# Resistor_Board.net
KiCad netlist of a schematic drawn in EAGLE
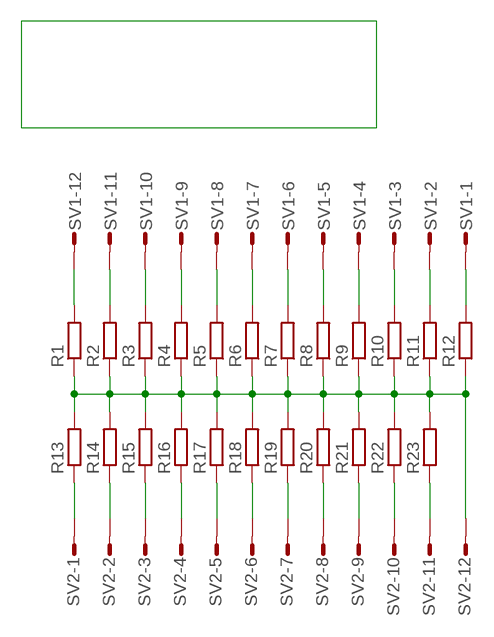
[diagram p0: schematic, sheet 1]

(export (version "E")
  (design (tool "Eeschema 10.0.6"))
  (components
    (comp (ref "R1")
      (value "R-EU_0207/10")
      (footprint "eagle-import:0207_10")
      (libsource (lib "eagle-import") (part "R-EU_0207/10"))
    )
    (comp (ref "R2")
      (value "R-EU_0207/10")
      (footprint "eagle-import:0207_10")
      (libsource (lib "eagle-import") (part "R-EU_0207/10"))
    )
    (comp (ref "R3")
      (value "R-EU_0207/10")
      (footprint "eagle-import:0207_10")
      (libsource (lib "eagle-import") (part "R-EU_0207/10"))
    )
    (comp (ref "R4")
      (value "R-EU_0207/10")
      (footprint "eagle-import:0207_10")
      (libsource (lib "eagle-import") (part "R-EU_0207/10"))
    )
    (comp (ref "R5")
      (value "R-EU_0207/10")
      (footprint "eagle-import:0207_10")
      (libsource (lib "eagle-import") (part "R-EU_0207/10"))
    )
    (comp (ref "R6")
      (value "R-EU_0207/10")
      (footprint "eagle-import:0207_10")
      (libsource (lib "eagle-import") (part "R-EU_0207/10"))
    )
    (comp (ref "R7")
      (value "R-EU_0207/10")
      (footprint "eagle-import:0207_10")
      (libsource (lib "eagle-import") (part "R-EU_0207/10"))
    )
    (comp (ref "R8")
      (value "R-EU_0207/10")
      (footprint "eagle-import:0207_10")
      (libsource (lib "eagle-import") (part "R-EU_0207/10"))
    )
    (comp (ref "R9")
      (value "R-EU_0207/10")
      (footprint "eagle-import:0207_10")
      (libsource (lib "eagle-import") (part "R-EU_0207/10"))
    )
    (comp (ref "R10")
      (value "R-EU_0207/10")
      (footprint "eagle-import:0207_10")
      (libsource (lib "eagle-import") (part "R-EU_0207/10"))
    )
    (comp (ref "R11")
      (value "R-EU_0207/10")
      (footprint "eagle-import:0207_10")
      (libsource (lib "eagle-import") (part "R-EU_0207/10"))
    )
    (comp (ref "R12")
      (value "R-EU_0207/10")
      (footprint "eagle-import:0207_10")
      (libsource (lib "eagle-import") (part "R-EU_0207/10"))
    )
    (comp (ref "R13")
      (value "R-EU_0207/10")
      (footprint "eagle-import:0207_10")
      (libsource (lib "eagle-import") (part "R-EU_0207/10"))
    )
    (comp (ref "R14")
      (value "R-EU_0207/10")
      (footprint "eagle-import:0207_10")
      (libsource (lib "eagle-import") (part "R-EU_0207/10"))
    )
    (comp (ref "R15")
      (value "R-EU_0207/10")
      (footprint "eagle-import:0207_10")
      (libsource (lib "eagle-import") (part "R-EU_0207/10"))
    )
    (comp (ref "R16")
      (value "R-EU_0207/10")
      (footprint "eagle-import:0207_10")
      (libsource (lib "eagle-import") (part "R-EU_0207/10"))
    )
    (comp (ref "R17")
      (value "R-EU_0207/10")
      (footprint "eagle-import:0207_10")
      (libsource (lib "eagle-import") (part "R-EU_0207/10"))
    )
    (comp (ref "R18")
      (value "R-EU_0207/10")
      (footprint "eagle-import:0207_10")
      (libsource (lib "eagle-import") (part "R-EU_0207/10"))
    )
    (comp (ref "R19")
      (value "R-EU_0207/10")
      (footprint "eagle-import:0207_10")
      (libsource (lib "eagle-import") (part "R-EU_0207/10"))
    )
    (comp (ref "R20")
      (value "R-EU_0207/10")
      (footprint "eagle-import:0207_10")
      (libsource (lib "eagle-import") (part "R-EU_0207/10"))
    )
    (comp (ref "R21")
      (value "R-EU_0207/10")
      (footprint "eagle-import:0207_10")
      (libsource (lib "eagle-import") (part "R-EU_0207/10"))
    )
    (comp (ref "R22")
      (value "R-EU_0207/10")
      (footprint "eagle-import:0207_10")
      (libsource (lib "eagle-import") (part "R-EU_0207/10"))
    )
    (comp (ref "R23")
      (value "R-EU_0207/10")
      (footprint "eagle-import:0207_10")
      (libsource (lib "eagle-import") (part "R-EU_0207/10"))
    )
    (comp (ref "SV1")
      (value "S12P")
      (footprint "eagle-import:S12P")
      (libsource (lib "eagle-import") (part "S12P"))
    )
    (comp (ref "SV2")
      (value "S12P")
      (footprint "eagle-import:S12P")
      (libsource (lib "eagle-import") (part "S12P"))
    )
  )
  (nets
    (net (code "1") (name "Net-(SV1A-S)") (class "Default")
      (node (ref "R12") (pin "2") (pinfunction "2_2") (pintype "passive"))
      (node (ref "SV1") (pin "1") (pinfunction "S_1") (pintype "passive"))
    )
    (net (code "2") (name "Net-(SV1B-S)") (class "Default")
      (node (ref "R3") (pin "2") (pinfunction "2_2") (pintype "passive"))
      (node (ref "SV1") (pin "10") (pinfunction "S_10") (pintype "passive"))
    )
    (net (code "3") (name "Net-(SV1C-S)") (class "Default")
      (node (ref "R2") (pin "2") (pinfunction "2_2") (pintype "passive"))
      (node (ref "SV1") (pin "11") (pinfunction "S_11") (pintype "passive"))
    )
    (net (code "4") (name "Net-(SV1D-S)") (class "Default")
      (node (ref "R1") (pin "2") (pinfunction "2_2") (pintype "passive"))
      (node (ref "SV1") (pin "12") (pinfunction "S_12") (pintype "passive"))
    )
    (net (code "5") (name "Net-(SV1E-S)") (class "Default")
      (node (ref "R11") (pin "2") (pinfunction "2_2") (pintype "passive"))
      (node (ref "SV1") (pin "2") (pinfunction "S_2") (pintype "passive"))
    )
    (net (code "6") (name "Net-(SV1F-S)") (class "Default")
      (node (ref "R10") (pin "2") (pinfunction "2_2") (pintype "passive"))
      (node (ref "SV1") (pin "3") (pinfunction "S_3") (pintype "passive"))
    )
    (net (code "7") (name "Net-(SV1G-S)") (class "Default")
      (node (ref "R9") (pin "2") (pinfunction "2_2") (pintype "passive"))
      (node (ref "SV1") (pin "4") (pinfunction "S_4") (pintype "passive"))
    )
    (net (code "8") (name "Net-(SV1H-S)") (class "Default")
      (node (ref "R8") (pin "2") (pinfunction "2_2") (pintype "passive"))
      (node (ref "SV1") (pin "5") (pinfunction "S_5") (pintype "passive"))
    )
    (net (code "9") (name "Net-(SV1I-S)") (class "Default")
      (node (ref "R7") (pin "2") (pinfunction "2_2") (pintype "passive"))
      (node (ref "SV1") (pin "6") (pinfunction "S_6") (pintype "passive"))
    )
    (net (code "10") (name "Net-(SV1J-S)") (class "Default")
      (node (ref "R6") (pin "2") (pinfunction "2_2") (pintype "passive"))
      (node (ref "SV1") (pin "7") (pinfunction "S_7") (pintype "passive"))
    )
    (net (code "11") (name "Net-(SV1K-S)") (class "Default")
      (node (ref "R5") (pin "2") (pinfunction "2_2") (pintype "passive"))
      (node (ref "SV1") (pin "8") (pinfunction "S_8") (pintype "passive"))
    )
    (net (code "12") (name "Net-(SV1L-S)") (class "Default")
      (node (ref "R4") (pin "2") (pinfunction "2_2") (pintype "passive"))
      (node (ref "SV1") (pin "9") (pinfunction "S_9") (pintype "passive"))
    )
    (net (code "13") (name "Net-(SV2A-S)") (class "Default")
      (node (ref "R13") (pin "1") (pinfunction "1_1") (pintype "passive"))
      (node (ref "SV2") (pin "1") (pinfunction "S_1") (pintype "passive"))
    )
    (net (code "14") (name "Net-(SV2B-S)") (class "Default")
      (node (ref "R22") (pin "1") (pinfunction "1_1") (pintype "passive"))
      (node (ref "SV2") (pin "10") (pinfunction "S_10") (pintype "passive"))
    )
    (net (code "15") (name "Net-(SV2C-S)") (class "Default")
      (node (ref "R23") (pin "1") (pinfunction "1_1") (pintype "passive"))
      (node (ref "SV2") (pin "11") (pinfunction "S_11") (pintype "passive"))
    )
    (net (code "16") (name "Net-(SV2D-S)") (class "Default")
      (node (ref "R1") (pin "1") (pinfunction "1_1") (pintype "passive"))
      (node (ref "R10") (pin "1") (pinfunction "1_1") (pintype "passive"))
      (node (ref "R11") (pin "1") (pinfunction "1_1") (pintype "passive"))
      (node (ref "R12") (pin "1") (pinfunction "1_1") (pintype "passive"))
      (node (ref "R13") (pin "2") (pinfunction "2_2") (pintype "passive"))
      (node (ref "R14") (pin "2") (pinfunction "2_2") (pintype "passive"))
      (node (ref "R15") (pin "2") (pinfunction "2_2") (pintype "passive"))
      (node (ref "R16") (pin "2") (pinfunction "2_2") (pintype "passive"))
      (node (ref "R17") (pin "2") (pinfunction "2_2") (pintype "passive"))
      (node (ref "R18") (pin "2") (pinfunction "2_2") (pintype "passive"))
      (node (ref "R19") (pin "2") (pinfunction "2_2") (pintype "passive"))
      (node (ref "R2") (pin "1") (pinfunction "1_1") (pintype "passive"))
      (node (ref "R20") (pin "2") (pinfunction "2_2") (pintype "passive"))
      (node (ref "R21") (pin "2") (pinfunction "2_2") (pintype "passive"))
      (node (ref "R22") (pin "2") (pinfunction "2_2") (pintype "passive"))
      (node (ref "R23") (pin "2") (pinfunction "2_2") (pintype "passive"))
      (node (ref "R3") (pin "1") (pinfunction "1_1") (pintype "passive"))
      (node (ref "R4") (pin "1") (pinfunction "1_1") (pintype "passive"))
      (node (ref "R5") (pin "1") (pinfunction "1_1") (pintype "passive"))
      (node (ref "R6") (pin "1") (pinfunction "1_1") (pintype "passive"))
      (node (ref "R7") (pin "1") (pinfunction "1_1") (pintype "passive"))
      (node (ref "R8") (pin "1") (pinfunction "1_1") (pintype "passive"))
      (node (ref "R9") (pin "1") (pinfunction "1_1") (pintype "passive"))
      (node (ref "SV2") (pin "12") (pinfunction "S_12") (pintype "passive"))
    )
    (net (code "17") (name "Net-(SV2E-S)") (class "Default")
      (node (ref "R14") (pin "1") (pinfunction "1_1") (pintype "passive"))
      (node (ref "SV2") (pin "2") (pinfunction "S_2") (pintype "passive"))
    )
    (net (code "18") (name "Net-(SV2F-S)") (class "Default")
      (node (ref "R15") (pin "1") (pinfunction "1_1") (pintype "passive"))
      (node (ref "SV2") (pin "3") (pinfunction "S_3") (pintype "passive"))
    )
    (net (code "19") (name "Net-(SV2G-S)") (class "Default")
      (node (ref "R16") (pin "1") (pinfunction "1_1") (pintype "passive"))
      (node (ref "SV2") (pin "4") (pinfunction "S_4") (pintype "passive"))
    )
    (net (code "20") (name "Net-(SV2H-S)") (class "Default")
      (node (ref "R17") (pin "1") (pinfunction "1_1") (pintype "passive"))
      (node (ref "SV2") (pin "5") (pinfunction "S_5") (pintype "passive"))
    )
    (net (code "21") (name "Net-(SV2I-S)") (class "Default")
      (node (ref "R18") (pin "1") (pinfunction "1_1") (pintype "passive"))
      (node (ref "SV2") (pin "6") (pinfunction "S_6") (pintype "passive"))
    )
    (net (code "22") (name "Net-(SV2J-S)") (class "Default")
      (node (ref "R19") (pin "1") (pinfunction "1_1") (pintype "passive"))
      (node (ref "SV2") (pin "7") (pinfunction "S_7") (pintype "passive"))
    )
    (net (code "23") (name "Net-(SV2K-S)") (class "Default")
      (node (ref "R20") (pin "1") (pinfunction "1_1") (pintype "passive"))
      (node (ref "SV2") (pin "8") (pinfunction "S_8") (pintype "passive"))
    )
    (net (code "24") (name "Net-(SV2L-S)") (class "Default")
      (node (ref "R21") (pin "1") (pinfunction "1_1") (pintype "passive"))
      (node (ref "SV2") (pin "9") (pinfunction "S_9") (pintype "passive"))
    )
  )
)
